# Octi.net
KiCad netlist of a schematic drawn in EAGLE
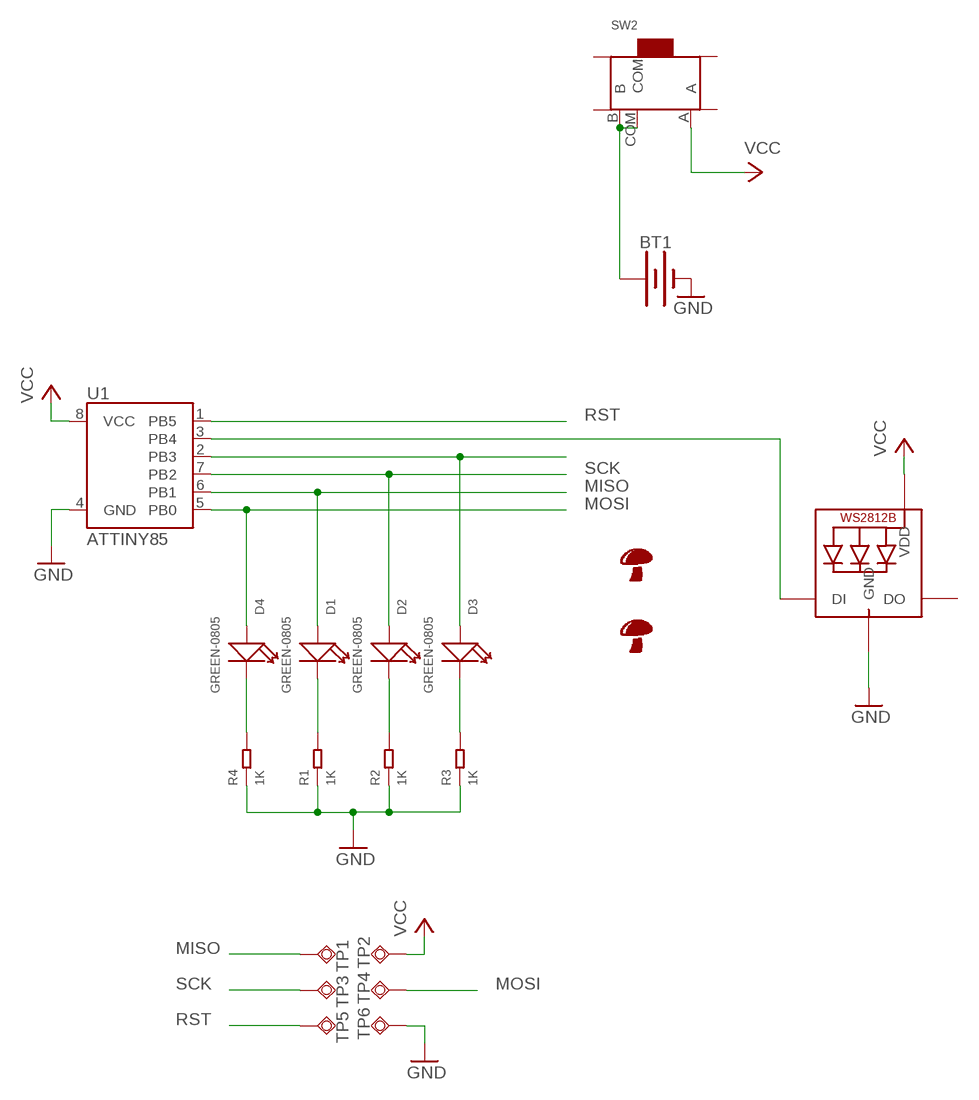
[diagram p0: schematic, sheet 1]

(export (version "E")
  (design (tool "Eeschema 10.0.6"))
  (components
    (comp (ref "BT1")
      (value "BATTERY-20MM_SMD")
      (footprint "eagle-import:BATTCON_20MM")
      (libsource (lib "eagle-import") (part "BATTERY-20MM_SMD"))
    )
    (comp (ref "D1")
      (value "GREEN-0805")
      (footprint "eagle-import:LED-0805")
      (fields (field (name "MPN") "17-215SYGC/S530-E2/TR8"))
      (libsource (lib "eagle-import") (part "SMD-LED-CLEAR-GREEN(0805)"))
    )
    (comp (ref "D2")
      (value "GREEN-0805")
      (footprint "eagle-import:LED-0805")
      (fields (field (name "MPN") "17-215SYGC/S530-E2/TR8"))
      (libsource (lib "eagle-import") (part "SMD-LED-CLEAR-GREEN(0805)"))
    )
    (comp (ref "D3")
      (value "GREEN-0805")
      (footprint "eagle-import:LED-0805")
      (fields (field (name "MPN") "17-215SYGC/S530-E2/TR8"))
      (libsource (lib "eagle-import") (part "SMD-LED-CLEAR-GREEN(0805)"))
    )
    (comp (ref "D4")
      (value "GREEN-0805")
      (footprint "eagle-import:LED-0805")
      (fields (field (name "MPN") "17-215SYGC/S530-E2/TR8"))
      (libsource (lib "eagle-import") (part "SMD-LED-CLEAR-GREEN(0805)"))
    )
    (comp (ref "LED1")
      (value "WS2812B5050")
      (footprint "eagle-import:WS2812B")
      (libsource (lib "eagle-import") (part "WS2812B5050"))
    )
    (comp (ref "R1")
      (value "1K")
      (footprint "eagle-import:R0603")
      (fields (field (name "MPN") "RC0603FR-071KL"))
      (libsource (lib "eagle-import") (part "SMD-RES-1K-1%-1/10W(0603)"))
    )
    (comp (ref "R2")
      (value "1K")
      (footprint "eagle-import:R0603")
      (fields (field (name "MPN") "RC0603FR-071KL"))
      (libsource (lib "eagle-import") (part "SMD-RES-1K-1%-1/10W(0603)"))
    )
    (comp (ref "R3")
      (value "1K")
      (footprint "eagle-import:R0603")
      (fields (field (name "MPN") "RC0603FR-071KL"))
      (libsource (lib "eagle-import") (part "SMD-RES-1K-1%-1/10W(0603)"))
    )
    (comp (ref "R4")
      (value "1K")
      (footprint "eagle-import:R0603")
      (fields (field (name "MPN") "RC0603FR-071KL"))
      (libsource (lib "eagle-import") (part "SMD-RES-1K-1%-1/10W(0603)"))
    )
    (comp (ref "SW2")
      (value "SMD-TOGGLE-SWITCH-ON-ON(3+4P-6.7X2.7MM)MOD")
      (footprint "eagle-import:SW7-MOD")
      (libsource (lib "eagle-import") (part "SMD-TOGGLE-SWITCH-ON-ON(3+4P-6.7X2.7MM)MOD"))
    )
    (comp (ref "TP1")
      (value "TPSQTP12SQ")
      (footprint "eagle-import:TP12SQ")
      (libsource (lib "eagle-import") (part "TPSQTP12SQ"))
    )
    (comp (ref "TP2")
      (value "TPSQTP12R")
      (footprint "eagle-import:TP12R")
      (libsource (lib "eagle-import") (part "TPSQTP12R"))
    )
    (comp (ref "TP3")
      (value "TPSQTP12R")
      (footprint "eagle-import:TP12R")
      (libsource (lib "eagle-import") (part "TPSQTP12R"))
    )
    (comp (ref "TP4")
      (value "TPSQTP12R")
      (footprint "eagle-import:TP12R")
      (libsource (lib "eagle-import") (part "TPSQTP12R"))
    )
    (comp (ref "TP5")
      (value "TPSQTP12R")
      (footprint "eagle-import:TP12R")
      (libsource (lib "eagle-import") (part "TPSQTP12R"))
    )
    (comp (ref "TP6")
      (value "TPSQTP12R")
      (footprint "eagle-import:TP12R")
      (libsource (lib "eagle-import") (part "TPSQTP12R"))
    )
    (comp (ref "U$1")
      (value "SHROOMBOTTOMSILK")
      (footprint "eagle-import:SHROOM_BS")
      (libsource (lib "eagle-import") (part "SHROOMBOTTOMSILK"))
    )
    (comp (ref "U$2")
      (value "SHROOM5MM")
      (footprint "eagle-import:SHROOM")
      (libsource (lib "eagle-import") (part "SHROOM5MM"))
    )
    (comp (ref "U1")
      (value "ATTINY85")
      (footprint "eagle-import:ATTINY85")
      (libsource (lib "eagle-import") (part "ATTINY85"))
    )
  )
  (nets
    (net (code "1") (name "/MISO") (class "Default")
      (node (ref "D1") (pin "+") (pinfunction "+_+") (pintype "passive"))
      (node (ref "TP1") (pin "TP") (pinfunction "TP_TP") (pintype "input"))
      (node (ref "U1") (pin "6") (pinfunction "PB1_6") (pintype "bidirectional"))
    )
    (net (code "2") (name "/MOSI") (class "Default")
      (node (ref "D4") (pin "+") (pinfunction "+_+") (pintype "passive"))
      (node (ref "TP4") (pin "TP") (pinfunction "TP_TP") (pintype "input"))
      (node (ref "U1") (pin "5") (pinfunction "PB0_5") (pintype "bidirectional"))
    )
    (net (code "3") (name "/RST") (class "Default")
      (node (ref "TP5") (pin "TP") (pinfunction "TP_TP") (pintype "input"))
      (node (ref "U1") (pin "1") (pinfunction "PB5_1") (pintype "bidirectional"))
    )
    (net (code "4") (name "/SCK") (class "Default")
      (node (ref "D2") (pin "+") (pinfunction "+_+") (pintype "passive"))
      (node (ref "TP3") (pin "TP") (pinfunction "TP_TP") (pintype "input"))
      (node (ref "U1") (pin "7") (pinfunction "PB2_7") (pintype "bidirectional"))
    )
    (net (code "5") (name "GND") (class "Default")
      (node (ref "BT1") (pin "2") (pinfunction "-_2") (pintype "power_in"))
      (node (ref "LED1") (pin "3-GND") (pinfunction "GND_3-GND") (pintype "power_in"))
      (node (ref "R1") (pin "1") (pinfunction "1_1") (pintype "passive"))
      (node (ref "R2") (pin "1") (pinfunction "1_1") (pintype "passive"))
      (node (ref "R3") (pin "1") (pinfunction "1_1") (pintype "passive"))
      (node (ref "R4") (pin "1") (pinfunction "1_1") (pintype "passive"))
      (node (ref "TP6") (pin "TP") (pinfunction "TP_TP") (pintype "input"))
      (node (ref "U1") (pin "4") (pinfunction "GND_4") (pintype "bidirectional"))
    )
    (net (code "6") (name "Net-(BT1-+)") (class "Default")
      (node (ref "BT1") (pin "1") (pinfunction "+_1") (pintype "power_in"))
      (node (ref "SW2") (pin "B") (pinfunction "B_B") (pintype "bidirectional"))
      (node (ref "SW2") (pin "COM") (pinfunction "COM_COM") (pintype "bidirectional"))
    )
    (net (code "7") (name "Net-(D1-Pad-)") (class "Default")
      (node (ref "D1") (pin "-") (pinfunction "-_-") (pintype "passive"))
      (node (ref "R1") (pin "2") (pinfunction "2_2") (pintype "passive"))
    )
    (net (code "8") (name "Net-(D2-Pad-)") (class "Default")
      (node (ref "D2") (pin "-") (pinfunction "-_-") (pintype "passive"))
      (node (ref "R2") (pin "2") (pinfunction "2_2") (pintype "passive"))
    )
    (net (code "9") (name "Net-(D3-Pad-)") (class "Default")
      (node (ref "D3") (pin "-") (pinfunction "-_-") (pintype "passive"))
      (node (ref "R3") (pin "2") (pinfunction "2_2") (pintype "passive"))
    )
    (net (code "10") (name "Net-(D4-Pad-)") (class "Default")
      (node (ref "D4") (pin "-") (pinfunction "-_-") (pintype "passive"))
      (node (ref "R4") (pin "2") (pinfunction "2_2") (pintype "passive"))
    )
    (net (code "11") (name "Net-(LED1-DI)") (class "Default")
      (node (ref "LED1") (pin "4-DIN") (pinfunction "DI_4-DIN") (pintype "input"))
      (node (ref "U1") (pin "3") (pinfunction "PB4_3") (pintype "bidirectional"))
    )
    (net (code "12") (name "Net-(U1-PB3)") (class "Default")
      (node (ref "D3") (pin "+") (pinfunction "+_+") (pintype "passive"))
      (node (ref "U1") (pin "2") (pinfunction "PB3_2") (pintype "bidirectional"))
    )
    (net (code "13") (name "VCC") (class "Default")
      (node (ref "LED1") (pin "1-VDD") (pinfunction "VDD_1-VDD") (pintype "power_in"))
      (node (ref "SW2") (pin "A") (pinfunction "A_A") (pintype "bidirectional"))
      (node (ref "TP2") (pin "TP") (pinfunction "TP_TP") (pintype "input"))
      (node (ref "U1") (pin "8") (pinfunction "VCC_8") (pintype "bidirectional"))
    )
    (net (code "14") (name "unconnected-(LED1-DO-Pad2-DOUT)") (class "Default")
      (node (ref "LED1") (pin "2-DOUT") (pinfunction "DO_2-DOUT") (pintype "output"))
    )
    (net (code "15") (name "unconnected-(SW2-PadSS1)") (class "Default")
      (node (ref "SW2") (pin "SS1") (pinfunction "SS1_SS1") (pintype "bidirectional"))
    )
    (net (code "16") (name "unconnected-(SW2-PadSS2)") (class "Default")
      (node (ref "SW2") (pin "SS2") (pinfunction "SS2_SS2") (pintype "bidirectional"))
    )
    (net (code "17") (name "unconnected-(SW2-PadSS3)") (class "Default")
      (node (ref "SW2") (pin "SS3") (pinfunction "SS3_SS3") (pintype "bidirectional"))
    )
    (net (code "18") (name "unconnected-(SW2-PadSS4)") (class "Default")
      (node (ref "SW2") (pin "SS4") (pinfunction "SS4_SS4") (pintype "bidirectional"))
    )
  )
)
